# stm32f303.net
KiCad netlist of a schematic drawn in EAGLE
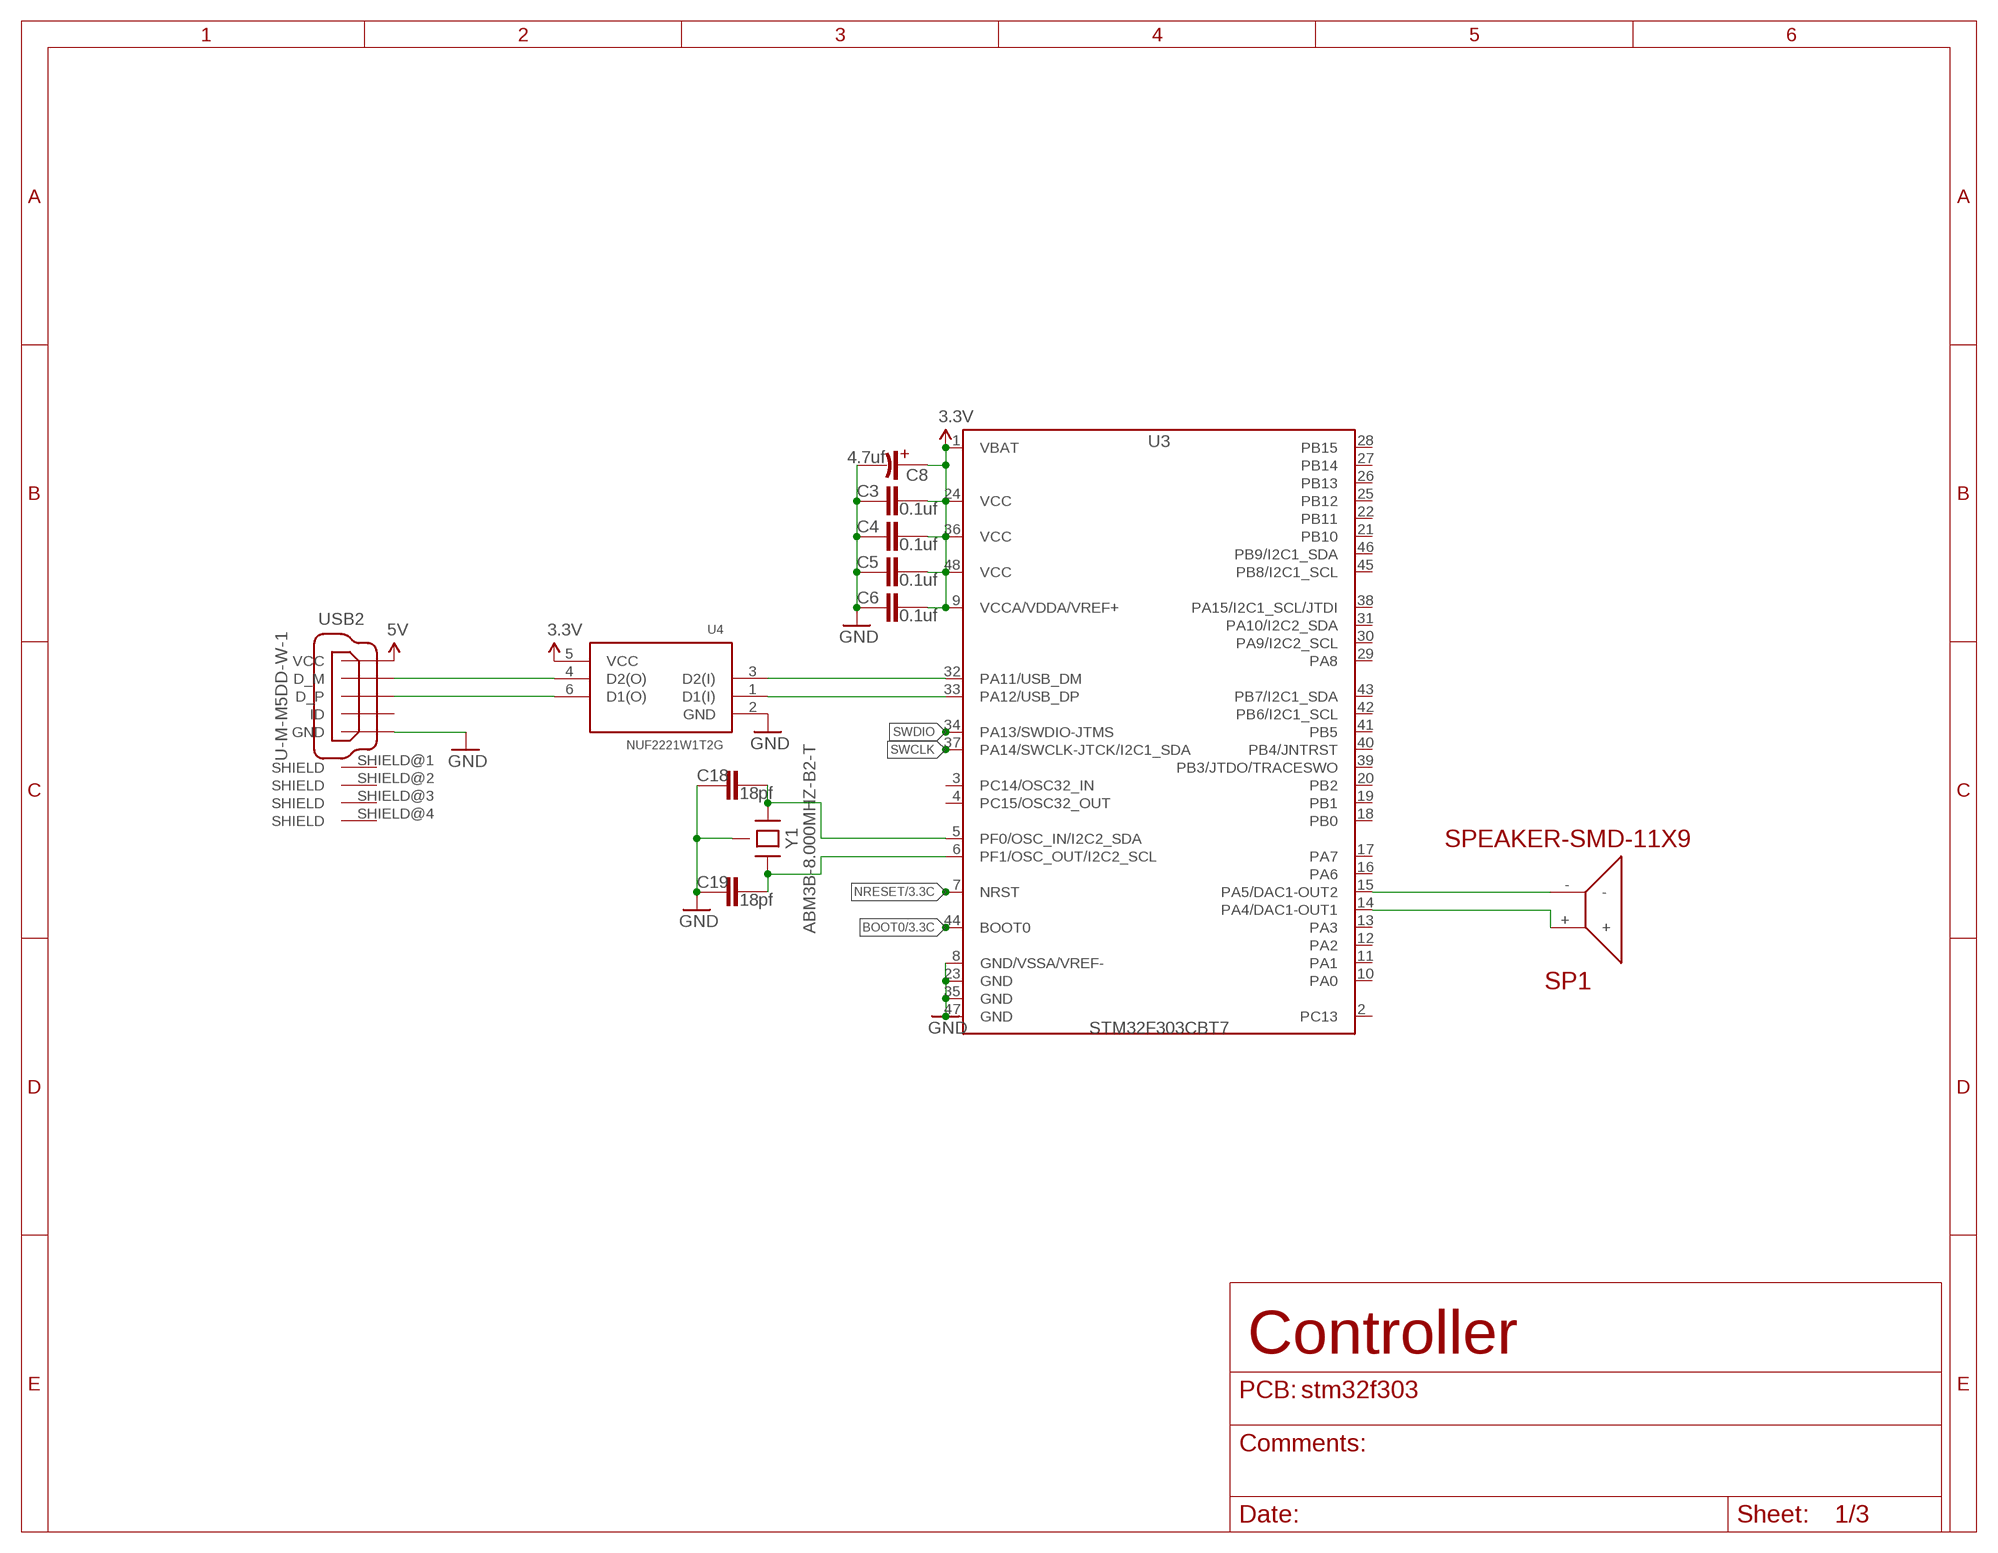
[diagram p0: schematic, sheet 1]
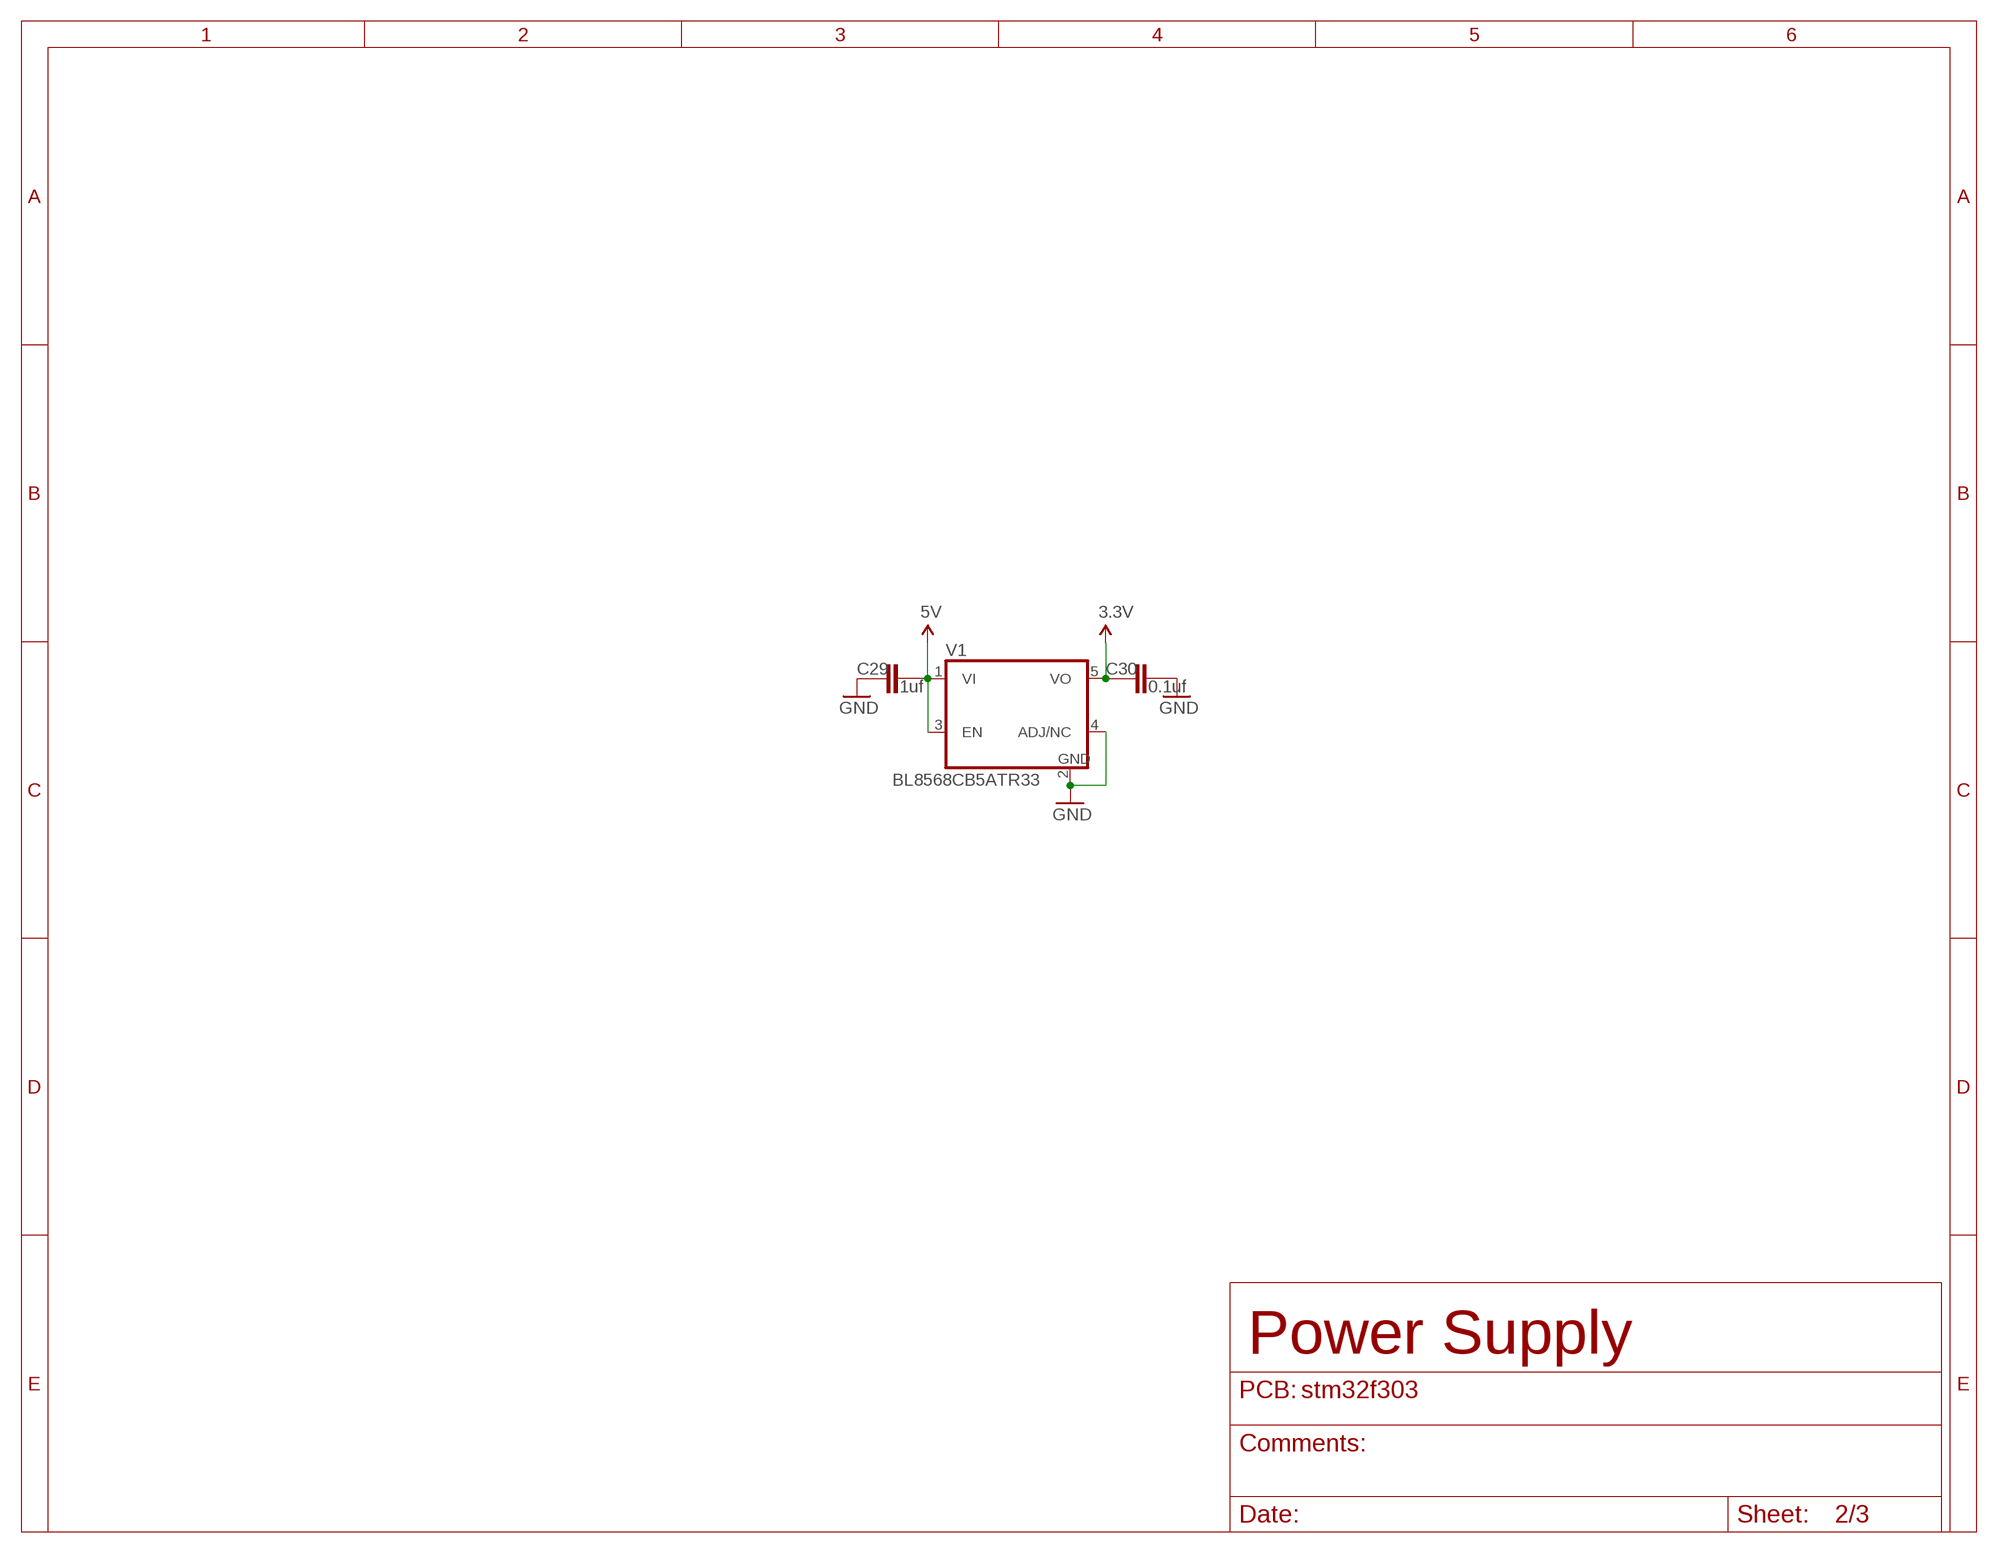
[diagram p1: schematic, sheet 2]
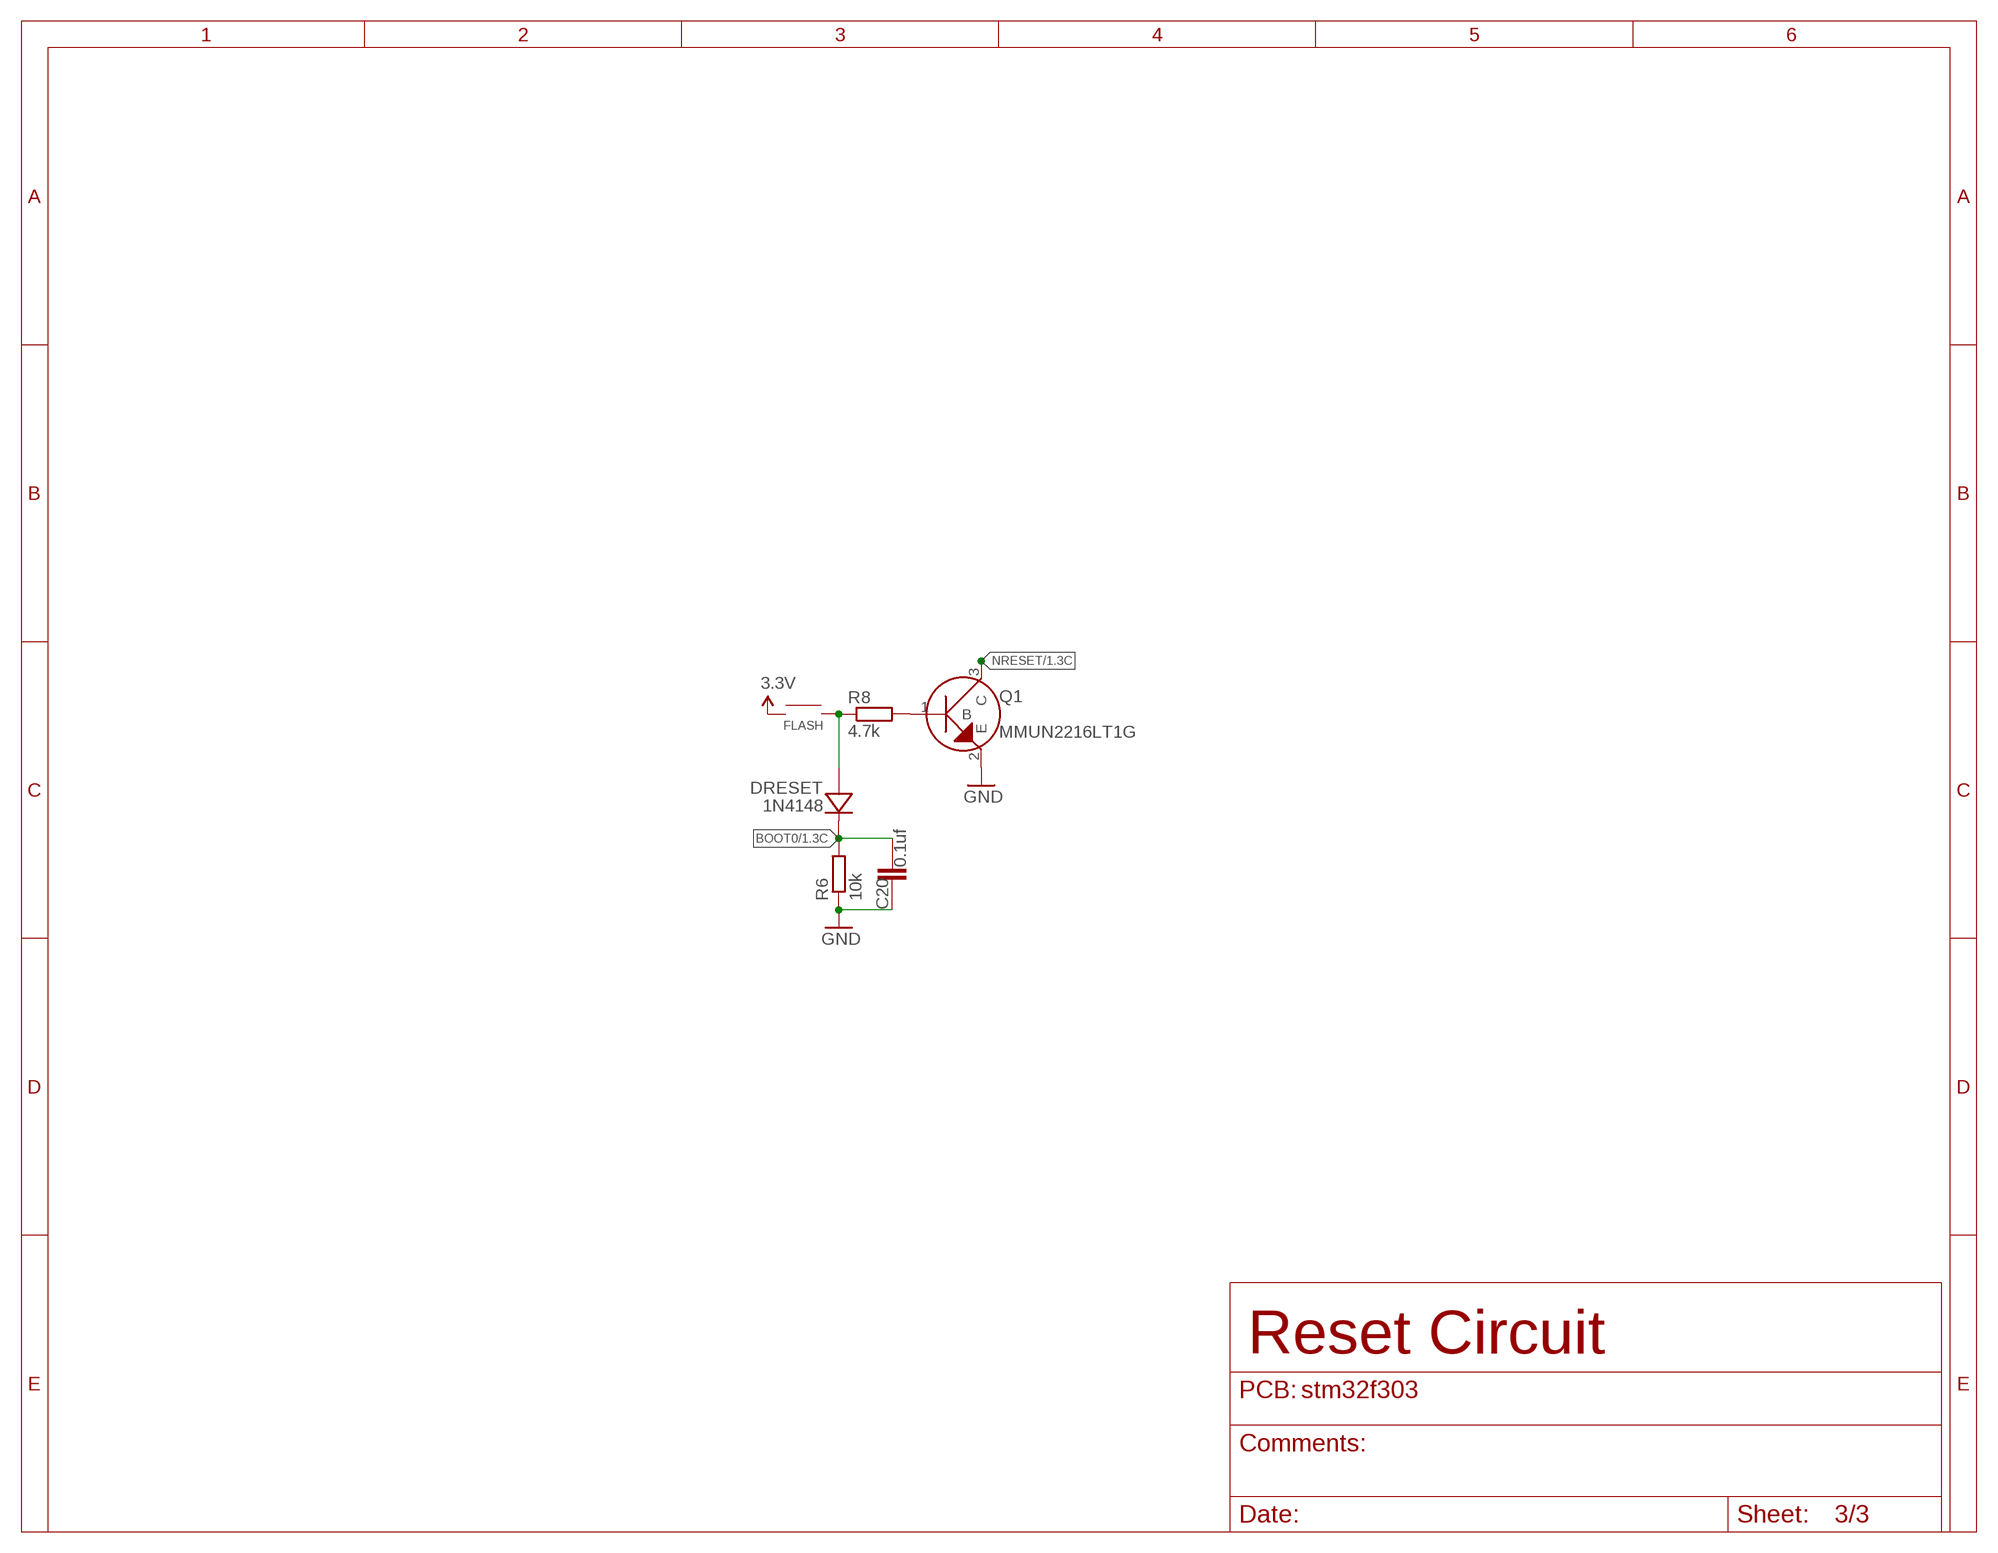
[diagram p2: schematic, sheet 3]

(export (version "E")
  (design (tool "Eeschema 10.0.6"))
  (components
    (comp (ref "C29")
      (value "1uf")
      (footprint "eagle-import:C0402")
      (libsource (lib "eagle-import") (part "CAPACITOR-0402"))
    )
    (comp (ref "C30")
      (value "0.1uf")
      (footprint "eagle-import:C0402")
      (libsource (lib "eagle-import") (part "CAPACITOR-0402"))
    )
    (comp (ref "V1")
      (value "BL8568CB5ATR33")
      (footprint "eagle-import:SOT-23-5")
      (libsource (lib "eagle-import") (part "LDO-VR"))
    )
    (comp (ref "C20")
      (value "0.1uf")
      (footprint "eagle-import:C0402")
      (libsource (lib "eagle-import") (part "CAPACITOR-0402"))
    )
    (comp (ref "DRESET")
      (value "1N4148")
      (footprint "eagle-import:SOD-123")
      (libsource (lib "eagle-import") (part "DIODE-SOD-123"))
    )
    (comp (ref "FLASH")
      (value "SKRPABE010")
      (footprint "eagle-import:SWITCH-SMD-SKRPABE010")
      (libsource (lib "eagle-import") (part "SWITCH-SMD-SKRPABE010"))
    )
    (comp (ref "Q1")
      (value "MMUN2216LT1G")
      (footprint "eagle-import:SOT-23-3")
      (libsource (lib "eagle-import") (part "TRANSISTOR-NPN"))
    )
    (comp (ref "R6")
      (value "10k")
      (footprint "eagle-import:R0402")
      (libsource (lib "eagle-import") (part "RESISTOR-0405"))
    )
    (comp (ref "R8")
      (value "4.7k")
      (footprint "eagle-import:R0402")
      (libsource (lib "eagle-import") (part "RESISTOR-0405"))
    )
    (comp (ref "C3")
      (value "0.1uf")
      (footprint "eagle-import:C0402")
      (libsource (lib "eagle-import") (part "CAPACITOR-0402"))
    )
    (comp (ref "C4")
      (value "0.1uf")
      (footprint "eagle-import:C0402")
      (libsource (lib "eagle-import") (part "CAPACITOR-0402"))
    )
    (comp (ref "C5")
      (value "0.1uf")
      (footprint "eagle-import:C0402")
      (libsource (lib "eagle-import") (part "CAPACITOR-0402"))
    )
    (comp (ref "C6")
      (value "0.1uf")
      (footprint "eagle-import:C0402")
      (libsource (lib "eagle-import") (part "CAPACITOR-0402"))
    )
    (comp (ref "C8")
      (value "4.7uf")
      (footprint "eagle-import:C0805-TANT")
      (libsource (lib "eagle-import") (part "CAPACITOR-TANT-0805"))
    )
    (comp (ref "C18")
      (value "18pf")
      (footprint "eagle-import:C0402")
      (libsource (lib "eagle-import") (part "CAPACITOR-0402"))
    )
    (comp (ref "C19")
      (value "18pf")
      (footprint "eagle-import:C0402")
      (libsource (lib "eagle-import") (part "CAPACITOR-0402"))
    )
    (comp (ref "SP1")
      (value "SPEAKER-SMD-11X9")
      (footprint "eagle-import:AST1109MLTRQ")
      (libsource (lib "eagle-import") (part "SPEAKER-SMD-11X9"))
    )
    (comp (ref "U3")
      (value "STM32F303CBT7")
      (footprint "eagle-import:LQFP48")
      (libsource (lib "eagle-import") (part "STM32F303CBT7"))
    )
    (comp (ref "U4")
      (value "NUF2221W1T2G")
      (footprint "eagle-import:SOT-363")
      (libsource (lib "eagle-import") (part "NUF221W1"))
    )
    (comp (ref "USB2")
      (value "U-M-M5DD-W-1")
      (footprint "eagle-import:U-M-M5DD-W-1")
      (libsource (lib "eagle-import") (part "USB_CONN-LCSC"))
    )
    (comp (ref "Y1")
      (value "ABM3B-8.000MHZ-B2-T")
      (footprint "eagle-import:CRYSTAL-3.2X5")
      (libsource (lib "eagle-import") (part "CRYSTAL-4PIN-3.2X5"))
    )
  )
  (nets
    (net (code "1") (name "3.3V") (class "Default")
      (node (ref "C3") (pin "2") (pinfunction "2_2") (pintype "passive"))
      (node (ref "C30") (pin "1") (pinfunction "1_1") (pintype "passive"))
      (node (ref "C4") (pin "2") (pinfunction "2_2") (pintype "passive"))
      (node (ref "C5") (pin "2") (pinfunction "2_2") (pintype "passive"))
      (node (ref "C6") (pin "2") (pinfunction "2_2") (pintype "passive"))
      (node (ref "C8") (pin "1") (pinfunction "+_1") (pintype "passive"))
      (node (ref "FLASH") (pin "1A") (pinfunction "1_1A") (pintype "passive"))
      (node (ref "FLASH") (pin "1B") (pinfunction "1_1B") (pintype "passive"))
      (node (ref "U3") (pin "1") (pinfunction "VBAT_1") (pintype "passive"))
      (node (ref "U3") (pin "24") (pinfunction "VCC_24") (pintype "passive"))
      (node (ref "U3") (pin "36") (pinfunction "VCC_36") (pintype "passive"))
      (node (ref "U3") (pin "48") (pinfunction "VCC_48") (pintype "passive"))
      (node (ref "U3") (pin "9") (pinfunction "VCCA/VDDA/VREF+_9") (pintype "passive"))
      (node (ref "U4") (pin "5") (pinfunction "VCC_5") (pintype "bidirectional"))
      (node (ref "V1") (pin "5") (pinfunction "VO_5") (pintype "passive"))
    )
    (net (code "2") (name "5V") (class "Default")
      (node (ref "C29") (pin "2") (pinfunction "2_2") (pintype "passive"))
      (node (ref "USB2") (pin "VCC") (pinfunction "VCC_VCC") (pintype "input"))
      (node (ref "V1") (pin "1") (pinfunction "VI_1") (pintype "input"))
      (node (ref "V1") (pin "3") (pinfunction "EN_3") (pintype "input"))
    )
    (net (code "3") (name "BOOT0") (class "Default")
      (node (ref "C20") (pin "2") (pinfunction "2_2") (pintype "passive"))
      (node (ref "DRESET") (pin "C") (pinfunction "C_C") (pintype "passive"))
      (node (ref "R6") (pin "2") (pinfunction "2_2") (pintype "passive"))
      (node (ref "U3") (pin "44") (pinfunction "BOOT0_44") (pintype "passive"))
    )
    (net (code "4") (name "GND") (class "Default")
      (node (ref "C18") (pin "1") (pinfunction "1_1") (pintype "passive"))
      (node (ref "C19") (pin "1") (pinfunction "1_1") (pintype "passive"))
      (node (ref "C20") (pin "1") (pinfunction "1_1") (pintype "passive"))
      (node (ref "C29") (pin "1") (pinfunction "1_1") (pintype "passive"))
      (node (ref "C3") (pin "1") (pinfunction "1_1") (pintype "passive"))
      (node (ref "C30") (pin "2") (pinfunction "2_2") (pintype "passive"))
      (node (ref "C4") (pin "1") (pinfunction "1_1") (pintype "passive"))
      (node (ref "C5") (pin "1") (pinfunction "1_1") (pintype "passive"))
      (node (ref "C6") (pin "1") (pinfunction "1_1") (pintype "passive"))
      (node (ref "C8") (pin "2") (pinfunction "-_2") (pintype "passive"))
      (node (ref "Q1") (pin "2") (pinfunction "E_2") (pintype "bidirectional"))
      (node (ref "R6") (pin "1") (pinfunction "1_1") (pintype "passive"))
      (node (ref "U3") (pin "23") (pinfunction "GND_23") (pintype "passive"))
      (node (ref "U3") (pin "35") (pinfunction "GND_35") (pintype "passive"))
      (node (ref "U3") (pin "47") (pinfunction "GND_47") (pintype "passive"))
      (node (ref "U3") (pin "8") (pinfunction "GND/VSSA/VREF-_8") (pintype "passive"))
      (node (ref "U4") (pin "2") (pinfunction "GND_2") (pintype "bidirectional"))
      (node (ref "USB2") (pin "GND") (pinfunction "GND_GND") (pintype "input"))
      (node (ref "V1") (pin "2") (pinfunction "GND_2") (pintype "passive"))
      (node (ref "V1") (pin "4") (pinfunction "ADJ/NC_4") (pintype "passive"))
      (node (ref "Y1") (pin "2") (pinfunction "GND_2") (pintype "bidirectional"))
      (node (ref "Y1") (pin "4") (pinfunction "GND_4") (pintype "bidirectional"))
    )
    (net (code "5") (name "NRESET") (class "Default")
      (node (ref "Q1") (pin "3") (pinfunction "C_3") (pintype "bidirectional"))
      (node (ref "U3") (pin "7") (pinfunction "NRST_7") (pintype "passive"))
    )
    (net (code "6") (name "Net-(DRESET-PadA)") (class "Default")
      (node (ref "DRESET") (pin "A") (pinfunction "A_A") (pintype "passive"))
      (node (ref "FLASH") (pin "2A") (pinfunction "2_2A") (pintype "passive"))
      (node (ref "FLASH") (pin "2B") (pinfunction "2_2B") (pintype "passive"))
      (node (ref "R8") (pin "1") (pinfunction "1_1") (pintype "passive"))
    )
    (net (code "7") (name "Net-(Q1-B)") (class "Default")
      (node (ref "Q1") (pin "1") (pinfunction "B_1") (pintype "bidirectional"))
      (node (ref "R8") (pin "2") (pinfunction "2_2") (pintype "passive"))
    )
    (net (code "8") (name "Net-(U3-PA4{slash}DAC1-OUT1)") (class "Default")
      (node (ref "SP1") (pin "+") (pinfunction "+_+") (pintype "bidirectional"))
      (node (ref "U3") (pin "14") (pinfunction "PA4/DAC1-OUT1_14") (pintype "passive"))
    )
    (net (code "9") (name "Net-(U3-PA5{slash}DAC1-OUT2)") (class "Default")
      (node (ref "SP1") (pin "-") (pinfunction "-_-") (pintype "bidirectional"))
      (node (ref "U3") (pin "15") (pinfunction "PA5/DAC1-OUT2_15") (pintype "passive"))
    )
    (net (code "10") (name "Net-(U3-PA11{slash}USB_DM)") (class "Default")
      (node (ref "U3") (pin "32") (pinfunction "PA11/USB_DM_32") (pintype "passive"))
      (node (ref "U4") (pin "3") (pinfunction "D2(I)_3") (pintype "bidirectional"))
    )
    (net (code "11") (name "Net-(U3-PA12{slash}USB_DP)") (class "Default")
      (node (ref "U3") (pin "33") (pinfunction "PA12/USB_DP_33") (pintype "passive"))
      (node (ref "U4") (pin "1") (pinfunction "D1(I)_1") (pintype "bidirectional"))
    )
    (net (code "12") (name "Net-(U3-PF0{slash}OSC_IN{slash}I2C2_SDA)") (class "Default")
      (node (ref "C18") (pin "2") (pinfunction "2_2") (pintype "passive"))
      (node (ref "U3") (pin "5") (pinfunction "PF0/OSC_IN/I2C2_SDA_5") (pintype "passive"))
      (node (ref "Y1") (pin "3") (pinfunction "2_3") (pintype "passive"))
    )
    (net (code "13") (name "Net-(U3-PF1{slash}OSC_OUT{slash}I2C2_SCL)") (class "Default")
      (node (ref "C19") (pin "2") (pinfunction "2_2") (pintype "passive"))
      (node (ref "U3") (pin "6") (pinfunction "PF1/OSC_OUT/I2C2_SCL_6") (pintype "passive"))
      (node (ref "Y1") (pin "1") (pinfunction "1_1") (pintype "passive"))
    )
    (net (code "14") (name "Net-(U4-D1(O))") (class "Default")
      (node (ref "U4") (pin "6") (pinfunction "D1(O)_6") (pintype "bidirectional"))
      (node (ref "USB2") (pin "D+") (pinfunction "D_P_D+") (pintype "input"))
    )
    (net (code "15") (name "Net-(U4-D2(O))") (class "Default")
      (node (ref "U4") (pin "4") (pinfunction "D2(O)_4") (pintype "bidirectional"))
      (node (ref "USB2") (pin "D-") (pinfunction "D_M_D-") (pintype "input"))
    )
    (net (code "16") (name "SWCLK") (class "Default")
      (node (ref "U3") (pin "37") (pinfunction "PA14/SWCLK-JTCK/I2C1_SDA_37") (pintype "passive"))
    )
    (net (code "17") (name "SWDIO") (class "Default")
      (node (ref "U3") (pin "34") (pinfunction "PA13/SWDIO-JTMS_34") (pintype "passive"))
    )
    (net (code "18") (name "unconnected-(U3-PA0-Pad10)") (class "Default")
      (node (ref "U3") (pin "10") (pinfunction "PA0_10") (pintype "passive"))
    )
    (net (code "19") (name "unconnected-(U3-PA1-Pad11)") (class "Default")
      (node (ref "U3") (pin "11") (pinfunction "PA1_11") (pintype "passive"))
    )
    (net (code "20") (name "unconnected-(U3-PA2-Pad12)") (class "Default")
      (node (ref "U3") (pin "12") (pinfunction "PA2_12") (pintype "passive"))
    )
    (net (code "21") (name "unconnected-(U3-PA3-Pad13)") (class "Default")
      (node (ref "U3") (pin "13") (pinfunction "PA3_13") (pintype "passive"))
    )
    (net (code "22") (name "unconnected-(U3-PA6-Pad16)") (class "Default")
      (node (ref "U3") (pin "16") (pinfunction "PA6_16") (pintype "passive"))
    )
    (net (code "23") (name "unconnected-(U3-PA7-Pad17)") (class "Default")
      (node (ref "U3") (pin "17") (pinfunction "PA7_17") (pintype "passive"))
    )
    (net (code "24") (name "unconnected-(U3-PA8-Pad29)") (class "Default")
      (node (ref "U3") (pin "29") (pinfunction "PA8_29") (pintype "passive"))
    )
    (net (code "25") (name "unconnected-(U3-PA9{slash}I2C2_SCL-Pad30)") (class "Default")
      (node (ref "U3") (pin "30") (pinfunction "PA9/I2C2_SCL_30") (pintype "passive"))
    )
    (net (code "26") (name "unconnected-(U3-PA10{slash}I2C2_SDA-Pad31)") (class "Default")
      (node (ref "U3") (pin "31") (pinfunction "PA10/I2C2_SDA_31") (pintype "passive"))
    )
    (net (code "27") (name "unconnected-(U3-PA15{slash}I2C1_SCL{slash}JTDI-Pad38)") (class "Default")
      (node (ref "U3") (pin "38") (pinfunction "PA15/I2C1_SCL/JTDI_38") (pintype "passive"))
    )
    (net (code "28") (name "unconnected-(U3-PB0-Pad18)") (class "Default")
      (node (ref "U3") (pin "18") (pinfunction "PB0_18") (pintype "passive"))
    )
    (net (code "29") (name "unconnected-(U3-PB1-Pad19)") (class "Default")
      (node (ref "U3") (pin "19") (pinfunction "PB1_19") (pintype "passive"))
    )
    (net (code "30") (name "unconnected-(U3-PB2-Pad20)") (class "Default")
      (node (ref "U3") (pin "20") (pinfunction "PB2_20") (pintype "passive"))
    )
    (net (code "31") (name "unconnected-(U3-PB3{slash}JTDO{slash}TRACESWO-Pad39)") (class "Default")
      (node (ref "U3") (pin "39") (pinfunction "PB3/JTDO/TRACESWO_39") (pintype "passive"))
    )
    (net (code "32") (name "unconnected-(U3-PB4{slash}JNTRST-Pad40)") (class "Default")
      (node (ref "U3") (pin "40") (pinfunction "PB4/JNTRST_40") (pintype "passive"))
    )
    (net (code "33") (name "unconnected-(U3-PB5-Pad41)") (class "Default")
      (node (ref "U3") (pin "41") (pinfunction "PB5_41") (pintype "passive"))
    )
    (net (code "34") (name "unconnected-(U3-PB6{slash}I2C1_SCL-Pad42)") (class "Default")
      (node (ref "U3") (pin "42") (pinfunction "PB6/I2C1_SCL_42") (pintype "passive"))
    )
    (net (code "35") (name "unconnected-(U3-PB7{slash}I2C1_SDA-Pad43)") (class "Default")
      (node (ref "U3") (pin "43") (pinfunction "PB7/I2C1_SDA_43") (pintype "passive"))
    )
    (net (code "36") (name "unconnected-(U3-PB8{slash}I2C1_SCL-Pad45)") (class "Default")
      (node (ref "U3") (pin "45") (pinfunction "PB8/I2C1_SCL_45") (pintype "passive"))
    )
    (net (code "37") (name "unconnected-(U3-PB9{slash}I2C1_SDA-Pad46)") (class "Default")
      (node (ref "U3") (pin "46") (pinfunction "PB9/I2C1_SDA_46") (pintype "passive"))
    )
    (net (code "38") (name "unconnected-(U3-PB10-Pad21)") (class "Default")
      (node (ref "U3") (pin "21") (pinfunction "PB10_21") (pintype "passive"))
    )
    (net (code "39") (name "unconnected-(U3-PB11-Pad22)") (class "Default")
      (node (ref "U3") (pin "22") (pinfunction "PB11_22") (pintype "passive"))
    )
    (net (code "40") (name "unconnected-(U3-PB12-Pad25)") (class "Default")
      (node (ref "U3") (pin "25") (pinfunction "PB12_25") (pintype "passive"))
    )
    (net (code "41") (name "unconnected-(U3-PB13-Pad26)") (class "Default")
      (node (ref "U3") (pin "26") (pinfunction "PB13_26") (pintype "passive"))
    )
    (net (code "42") (name "unconnected-(U3-PB14-Pad27)") (class "Default")
      (node (ref "U3") (pin "27") (pinfunction "PB14_27") (pintype "passive"))
    )
    (net (code "43") (name "unconnected-(U3-PB15-Pad28)") (class "Default")
      (node (ref "U3") (pin "28") (pinfunction "PB15_28") (pintype "passive"))
    )
    (net (code "44") (name "unconnected-(U3-PC13-Pad2)") (class "Default")
      (node (ref "U3") (pin "2") (pinfunction "PC13_2") (pintype "passive"))
    )
    (net (code "45") (name "unconnected-(U3-PC14{slash}OSC32_IN-Pad3)") (class "Default")
      (node (ref "U3") (pin "3") (pinfunction "PC14/OSC32_IN_3") (pintype "passive"))
    )
    (net (code "46") (name "unconnected-(U3-PC15{slash}OSC32_OUT-Pad4)") (class "Default")
      (node (ref "U3") (pin "4") (pinfunction "PC15/OSC32_OUT_4") (pintype "passive"))
    )
    (net (code "47") (name "unconnected-(USB2-PadID)") (class "Default")
      (node (ref "USB2") (pin "ID") (pinfunction "ID_ID") (pintype "input"))
    )
    (net (code "48") (name "unconnected-(USB2-SHIELD-PadSHIELD@1)") (class "Default")
      (node (ref "USB2") (pin "SHIELD@1") (pinfunction "SHIELD_SHIELD@1") (pintype "bidirectional"))
    )
    (net (code "49") (name "unconnected-(USB2-SHIELD-PadSHIELD@2)") (class "Default")
      (node (ref "USB2") (pin "SHIELD@2") (pinfunction "SHIELD_SHIELD@2") (pintype "bidirectional"))
    )
    (net (code "50") (name "unconnected-(USB2-SHIELD-PadSHIELD@3)") (class "Default")
      (node (ref "USB2") (pin "SHIELD@3") (pinfunction "SHIELD_SHIELD@3") (pintype "bidirectional"))
    )
    (net (code "51") (name "unconnected-(USB2-SHIELD-PadSHIELD@4)") (class "Default")
      (node (ref "USB2") (pin "SHIELD@4") (pinfunction "SHIELD_SHIELD@4") (pintype "bidirectional"))
    )
  )
)
